# KURSUCH.net
KiCad netlist of a schematic drawn in Altium Designer
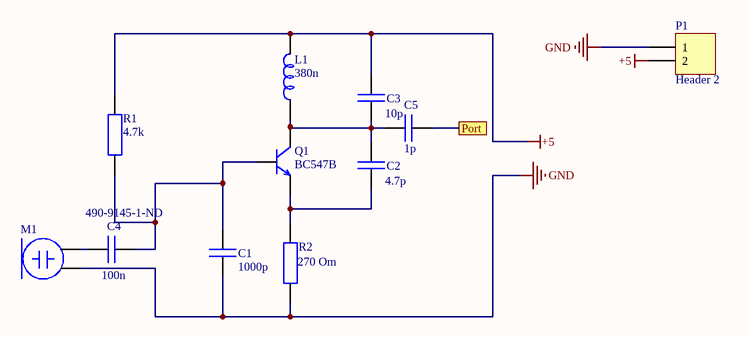
[diagram p0: KURSUCH.SchDoc]

(export (version "E")
  (design (tool "Eeschema 10.0.6"))
  (components
    (comp (ref "C1")
      (value "1000p")
      (footprint "Capacitor-2,5")
      (description "Cap Ceramic 1uF 16V X7R 10% Radial 5mm 125°C Bulk")
      (fields
        (field (name "MANUFACTURER") "TDK")
        (field (name "MANUFACTURER PART NUMBER") "FK24X7R1C105KN000")
      )
      (libsource (lib "component") (part "Capaciitor"))
    )
    (comp (ref "C2")
      (value "4.7p")
      (footprint "Capacitor-2,5")
      (description "Capacitor Ceramic 4.7pF 50V C0G 0.25pF 2.5mm T/R")
      (fields
        (field (name "MANUFACTURER") "TDK")
        (field (name "MANUFACTURER PART NUMBER") "FA18C0G1H4R7CNU06")
      )
      (libsource (lib "component") (part "Capaciitor"))
    )
    (comp (ref "C3")
      (value "10p")
      (footprint "Capacitor-2,5")
      (description "CAP CER 10PF 50V C0G RADIAL")
      (fields
        (field (name "MANUFACTURER") "TDK")
        (field (name "MANUFACTURER PART NUMBER") "FG18C0G1H100DNT06")
      )
      (libsource (lib "component") (part "Capaciitor"))
    )
    (comp (ref "C4")
      (value "100n")
      (footprint "Capacitor-2,5")
      (description "CAP CER 0.1UF 50V X7R RADIAL")
      (fields
        (field (name "SUPPLIER PART NUMBER 1") "490-9145-1-ND")
        (field (name "MANUFACTURER") "Murata")
        (field (name "MANUFACTURER PART NUMBER") "RDER71H104K0S1H03A")
      )
      (libsource (lib "component") (part "Capaciitor"))
    )
    (comp (ref "C5")
      (value "1p")
      (footprint "Capacitor-2,5")
      (description "Capacitor Ceramic 01pF 100V C0G 0.25pF 2.5mm Bulk")
      (fields
        (field (name "MANUFACTURER") "TDK")
        (field (name "MANUFACTURER PART NUMBER") "FA18C0G2A010CNU00")
      )
      (libsource (lib "component") (part "Capaciitor"))
    )
    (comp (ref "L1")
      (value "380n")
      (footprint "Inductor1")
      (description "FIXED IND 380NH 2.5A 25.5 MOHM")
      (fields
        (field (name "MANUFACTURER") "Abracon")
        (field (name "MANUFACTURER PART NUMBER") "AIAC-4125C-R380J-T")
      )
      (libsource (lib "component") (part "Inductor"))
    )
    (comp (ref "M1") (value "Mic") (footprint "Mic") (libsource (lib "component") (part "Mic")))
    (comp (ref "P1")
      (value "Header 2")
      (footprint "HDR1X2")
      (description "Header, 2-Pin")
      (fields (field (name "PUBLISHER") "Altium Limited"))
      (libsource (lib "Miscellaneous Connectors") (part "Header 2"))
    )
    (comp (ref "Q1")
      (value "BC547B")
      (footprint "Transistor")
      (fields (field (name "MANUFACTURER") "ON Semiconductor / Fairchild") (field (name "VOLTAGE") "40V"))
      (libsource (lib "component") (part "Transistor"))
    )
    (comp (ref "R1")
      (value "4.7k")
      (footprint "Resistor")
      (description "Res Metal Film 4.7K Ohm 2% 0.25W(1/4W) ±100ppm/C 0.01% Epoxy AXL Bulk")
      (fields
        (field (name "MANUFACTURER") "Vishay Dale")
        (field (name "MANUFACTURER PART NUMBER") "RLR07C4701GRB14")
      )
      (libsource (lib "component") (part "Resistor"))
    )
    (comp (ref "R2")
      (value "270 Om")
      (footprint "Resistor")
      (description "Res Carbon Film 270 Ohm 5% 0.125W(1/8W) -400ppm/C to 0ppm/C Conformal Coated AXL T/R")
      (fields
        (field (name "MANUFACTURER") "Stackpole Electronics")
        (field (name "MANUFACTURER PART NUMBER") "CF18JT270R")
      )
      (libsource (lib "component") (part "Resistor"))
    )
  )
  (nets
    (net (code "1") (name "+5") (class "Default")
      (node (ref "C3") (pin "2") (pinfunction "2_2") (pintype "passive"))
      (node (ref "L1") (pin "2") (pinfunction "2_2") (pintype "passive"))
      (node (ref "P1") (pin "2") (pinfunction "2_2") (pintype "passive"))
      (node (ref "R1") (pin "2") (pinfunction "2_2") (pintype "passive"))
    )
    (net (code "2") (name "/Port") (class "Default")
      (node (ref "C5") (pin "2") (pinfunction "2_2") (pintype "passive"))
    )
    (net (code "3") (name "GND") (class "Default")
      (node (ref "C1") (pin "1") (pinfunction "1_1") (pintype "passive"))
      (node (ref "M1") (pin "2") (pinfunction "2_2") (pintype "passive"))
      (node (ref "P1") (pin "1") (pinfunction "1_1") (pintype "passive"))
      (node (ref "R2") (pin "1") (pinfunction "1_1") (pintype "passive"))
    )
    (net (code "4") (name "Net-(C1-Pad2)") (class "Default")
      (node (ref "C1") (pin "2") (pinfunction "2_2") (pintype "passive"))
      (node (ref "C4") (pin "2") (pinfunction "2_2") (pintype "passive"))
      (node (ref "Q1") (pin "2") (pinfunction "2_2") (pintype "passive"))
      (node (ref "R1") (pin "1") (pinfunction "1_1") (pintype "passive"))
    )
    (net (code "5") (name "Net-(C2-Pad1)") (class "Default")
      (node (ref "C2") (pin "1") (pinfunction "1_1") (pintype "passive"))
      (node (ref "Q1") (pin "3") (pinfunction "3_3") (pintype "passive"))
      (node (ref "R2") (pin "2") (pinfunction "2_2") (pintype "passive"))
    )
    (net (code "6") (name "Net-(C2-Pad2)") (class "Default")
      (node (ref "C2") (pin "2") (pinfunction "2_2") (pintype "passive"))
      (node (ref "C3") (pin "1") (pinfunction "1_1") (pintype "passive"))
      (node (ref "C5") (pin "1") (pinfunction "1_1") (pintype "passive"))
      (node (ref "L1") (pin "1") (pinfunction "1_1") (pintype "passive"))
      (node (ref "Q1") (pin "1") (pinfunction "1_1") (pintype "passive"))
    )
    (net (code "7") (name "Net-(C4-Pad1)") (class "Default")
      (node (ref "C4") (pin "1") (pinfunction "1_1") (pintype "passive"))
      (node (ref "M1") (pin "1") (pinfunction "1_1") (pintype "passive"))
    )
  )
)
